# Payload.net
KiCad netlist of a schematic drawn in Altium Designer
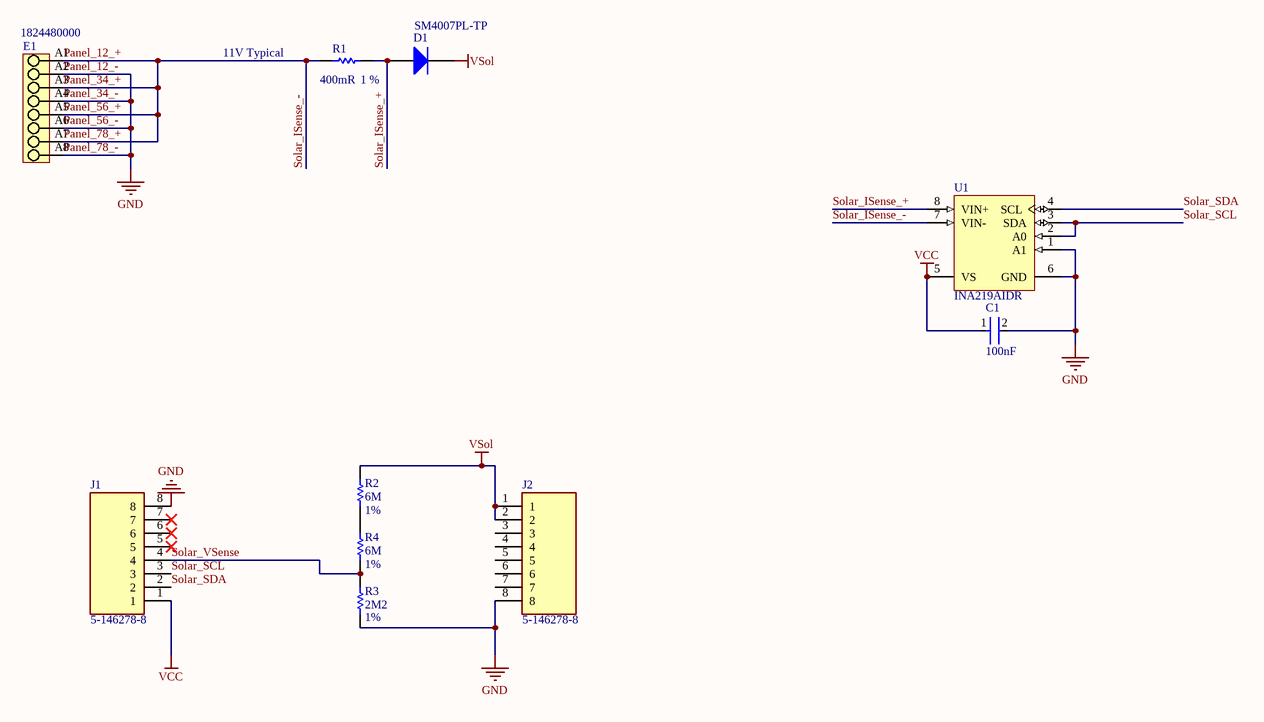
[diagram p0: Payload.SchDoc]

(export (version "E")
  (design (tool "Eeschema 10.0.6"))
  (components
    (comp (ref "C1")
      (value "100nF")
      (footprint "FP-0603-L_1_6_0_15-W_0_81-IPC_C")
      (description "Generic 0603 Capacitor")
      (fields (field (name "LCSC PART #") "C14663") (field (name "TOLERANCE") "10%"))
      (libsource (lib "StrathSEDS") (part "02cd4be3c70576c341d710602a673aa"))
    )
    (comp (ref "D1")
      (value "SM4007PL-TP")
      (footprint "MCC-SOD-123FL_V")
      (description "DIODE GEN PURP 1KV 1A SOD123FL")
      (fields (field (name "LCSC PART #") "C64898"))
      (libsource (lib "StrathSEDS") (part "D-AK-2"))
    )
    (comp (ref "E1")
      (value "1824480000")
      (footprint "LSF_SMT_3_5_90_08")
      (description "Weidmüller OMNIMATE Signal - series LSF LSF-SMT 3.50/08/90 3.5SN BK TU - 1824480000")
      (libsource (lib "StrathSEDS") (part "Terminal_08_1x08"))
    )
    (comp (ref "J1")
      (value "5-146278-8")
      (footprint "HDRV8W56P0X254_1X8_1991X234X872P")
      (description "08 MODII HDR SRST B/A .100CL")
      (fields (field (name "MOUSER PART NUMBER") "571-5-146278-8"))
      (libsource (lib "") (part "5-146278-8_1"))
    )
    (comp (ref "J2")
      (value "5-146278-8")
      (footprint "HDRV8W56P0X254_1X8_1991X234X872P")
      (description "08 MODII HDR SRST B/A .100CL")
      (fields (field (name "MOUSER PART NUMBER") "571-5-146278-8"))
      (libsource (lib "StrathSEDS") (part "5-146278-8"))
    )
    (comp (ref "R1")
      (value "400mR")
      (footprint "RESC2512(6432)_N")
      (description "931R 1W 1% 2512 (6432 Metric)  SMD")
      (fields
        (field (name "POWER") "1 W")
        (field (name "TOLERANCE") "1 %")
        (field (name "Comment") "Generic Resistor")
      )
      (libsource (lib "Altium Content Vault") (part "RES"))
    )
    (comp (ref "R2")
      (value "6M")
      (footprint "RESC1609X50X30ML8T20")
      (description "Generic 0603 Resistor")
      (fields
        (field (name "TOLERANCE") "1%")
        (field (name "LCSC PART #") "C322196")
        (field (name "Comment") "Generic-Resistor")
      )
      (libsource (lib "StrathSEDS") (part "RES-2"))
    )
    (comp (ref "R3")
      (value "2M2")
      (footprint "RESC1609X50X30ML8T20")
      (description "Generic 0603 Resistor")
      (fields
        (field (name "TOLERANCE") "1%")
        (field (name "LCSC PART #") "C322103")
        (field (name "Comment") "Generic-Resistor")
      )
      (libsource (lib "StrathSEDS") (part "RES-2"))
    )
    (comp (ref "R4")
      (value "6M")
      (footprint "RESC1609X50X30ML8T20")
      (description "Generic 0603 Resistor")
      (fields
        (field (name "TOLERANCE") "1%")
        (field (name "LCSC PART #") "C322196")
        (field (name "Comment") "Generic-Resistor")
      )
      (libsource (lib "StrathSEDS") (part "RES-2"))
    )
    (comp (ref "U1")
      (value "INA219AIDR")
      (footprint "D0008A_L")
      (description "Current Monitor Regulator High-Side 10mA 8-SOIC")
      (fields (field (name "LCSC PART #") "C138706"))
      (libsource (lib "StrathSEDS") (part "TI-INA219D8"))
    )
  )
  (nets
    (net (code "1") (name "/Panel_12_+") (class "Default")
      (node (ref "E1") (pin "A1") (pinfunction "A1_A1") (pintype "passive"))
      (node (ref "E1") (pin "A3") (pinfunction "A3_A3") (pintype "passive"))
      (node (ref "E1") (pin "A5") (pinfunction "A5_A5") (pintype "passive"))
      (node (ref "E1") (pin "A7") (pinfunction "A7_A7") (pintype "passive"))
      (node (ref "R1") (pin "1") (pinfunction "1_1") (pintype "passive"))
      (node (ref "U1") (pin "7") (pinfunction "VIN-_7") (pintype "input"))
    )
    (net (code "2") (name "/Solar_ISense_+") (class "Default")
      (node (ref "D1") (pin "1") (pinfunction "A_1") (pintype "passive"))
      (node (ref "R1") (pin "2") (pinfunction "2_2") (pintype "passive"))
      (node (ref "U1") (pin "8") (pinfunction "VIN+_8") (pintype "input"))
    )
    (net (code "3") (name "/Solar_SCL") (class "Default")
      (node (ref "J1") (pin "3") (pinfunction "3_3") (pintype "passive"))
      (node (ref "U1") (pin "2") (pinfunction "A0_2") (pintype "input"))
      (node (ref "U1") (pin "3") (pinfunction "SDA_3") (pintype "bidirectional"))
    )
    (net (code "4") (name "/Solar_SDA") (class "Default")
      (node (ref "J1") (pin "2") (pinfunction "2_2") (pintype "passive"))
      (node (ref "U1") (pin "4") (pinfunction "SCL_4") (pintype "bidirectional"))
    )
    (net (code "5") (name "/Solar_VSense") (class "Default")
      (node (ref "J1") (pin "4") (pinfunction "4_4") (pintype "passive"))
      (node (ref "R3") (pin "2") (pinfunction "2_2") (pintype "passive"))
      (node (ref "R4") (pin "1") (pinfunction "1_1") (pintype "passive"))
    )
    (net (code "6") (name "GND") (class "Default")
      (node (ref "C1") (pin "2") (pinfunction "2_2") (pintype "passive"))
      (node (ref "E1") (pin "A2") (pinfunction "A2_A2") (pintype "passive"))
      (node (ref "E1") (pin "A4") (pinfunction "A4_A4") (pintype "passive"))
      (node (ref "E1") (pin "A6") (pinfunction "A6_A6") (pintype "passive"))
      (node (ref "E1") (pin "A8") (pinfunction "A8_A8") (pintype "passive"))
      (node (ref "J1") (pin "8") (pinfunction "8_8") (pintype "passive"))
      (node (ref "J2") (pin "8") (pinfunction "8_8") (pintype "passive"))
      (node (ref "R3") (pin "1") (pinfunction "1_1") (pintype "passive"))
      (node (ref "U1") (pin "1") (pinfunction "A1_1") (pintype "input"))
      (node (ref "U1") (pin "6") (pinfunction "GND_6") (pintype "power_in"))
    )
    (net (code "7") (name "Net-(R2-Pad1)") (class "Default")
      (node (ref "R2") (pin "1") (pinfunction "1_1") (pintype "passive"))
      (node (ref "R4") (pin "2") (pinfunction "2_2") (pintype "passive"))
    )
    (net (code "8") (name "VCC") (class "Default")
      (node (ref "C1") (pin "1") (pinfunction "1_1") (pintype "passive"))
      (node (ref "J1") (pin "1") (pinfunction "1_1") (pintype "passive"))
      (node (ref "U1") (pin "5") (pinfunction "VS_5") (pintype "power_in"))
    )
    (net (code "9") (name "VSol") (class "Default")
      (node (ref "D1") (pin "2") (pinfunction "K_2") (pintype "passive"))
      (node (ref "J2") (pin "1") (pinfunction "1_1") (pintype "passive"))
      (node (ref "J2") (pin "2") (pinfunction "2_2") (pintype "passive"))
      (node (ref "R2") (pin "2") (pinfunction "2_2") (pintype "passive"))
    )
    (net (code "10") (name "unconnected-(J1-Pad5)") (class "Default")
      (node (ref "J1") (pin "5") (pinfunction "5_5") (pintype "passive+no_connect"))
    )
    (net (code "11") (name "unconnected-(J1-Pad6)") (class "Default")
      (node (ref "J1") (pin "6") (pinfunction "6_6") (pintype "passive+no_connect"))
    )
    (net (code "12") (name "unconnected-(J1-Pad7)") (class "Default")
      (node (ref "J1") (pin "7") (pinfunction "7_7") (pintype "passive+no_connect"))
    )
    (net (code "13") (name "unconnected-(J2-Pad3)") (class "Default")
      (node (ref "J2") (pin "3") (pinfunction "3_3") (pintype "passive"))
    )
    (net (code "14") (name "unconnected-(J2-Pad4)") (class "Default")
      (node (ref "J2") (pin "4") (pinfunction "4_4") (pintype "passive"))
    )
    (net (code "15") (name "unconnected-(J2-Pad5)") (class "Default")
      (node (ref "J2") (pin "5") (pinfunction "5_5") (pintype "passive"))
    )
    (net (code "16") (name "unconnected-(J2-Pad6)") (class "Default")
      (node (ref "J2") (pin "6") (pinfunction "6_6") (pintype "passive"))
    )
    (net (code "17") (name "unconnected-(J2-Pad7)") (class "Default")
      (node (ref "J2") (pin "7") (pinfunction "7_7") (pintype "passive"))
    )
  )
)
